# current_monitor_1_0_0.net
KiCad netlist of a schematic drawn in EAGLE
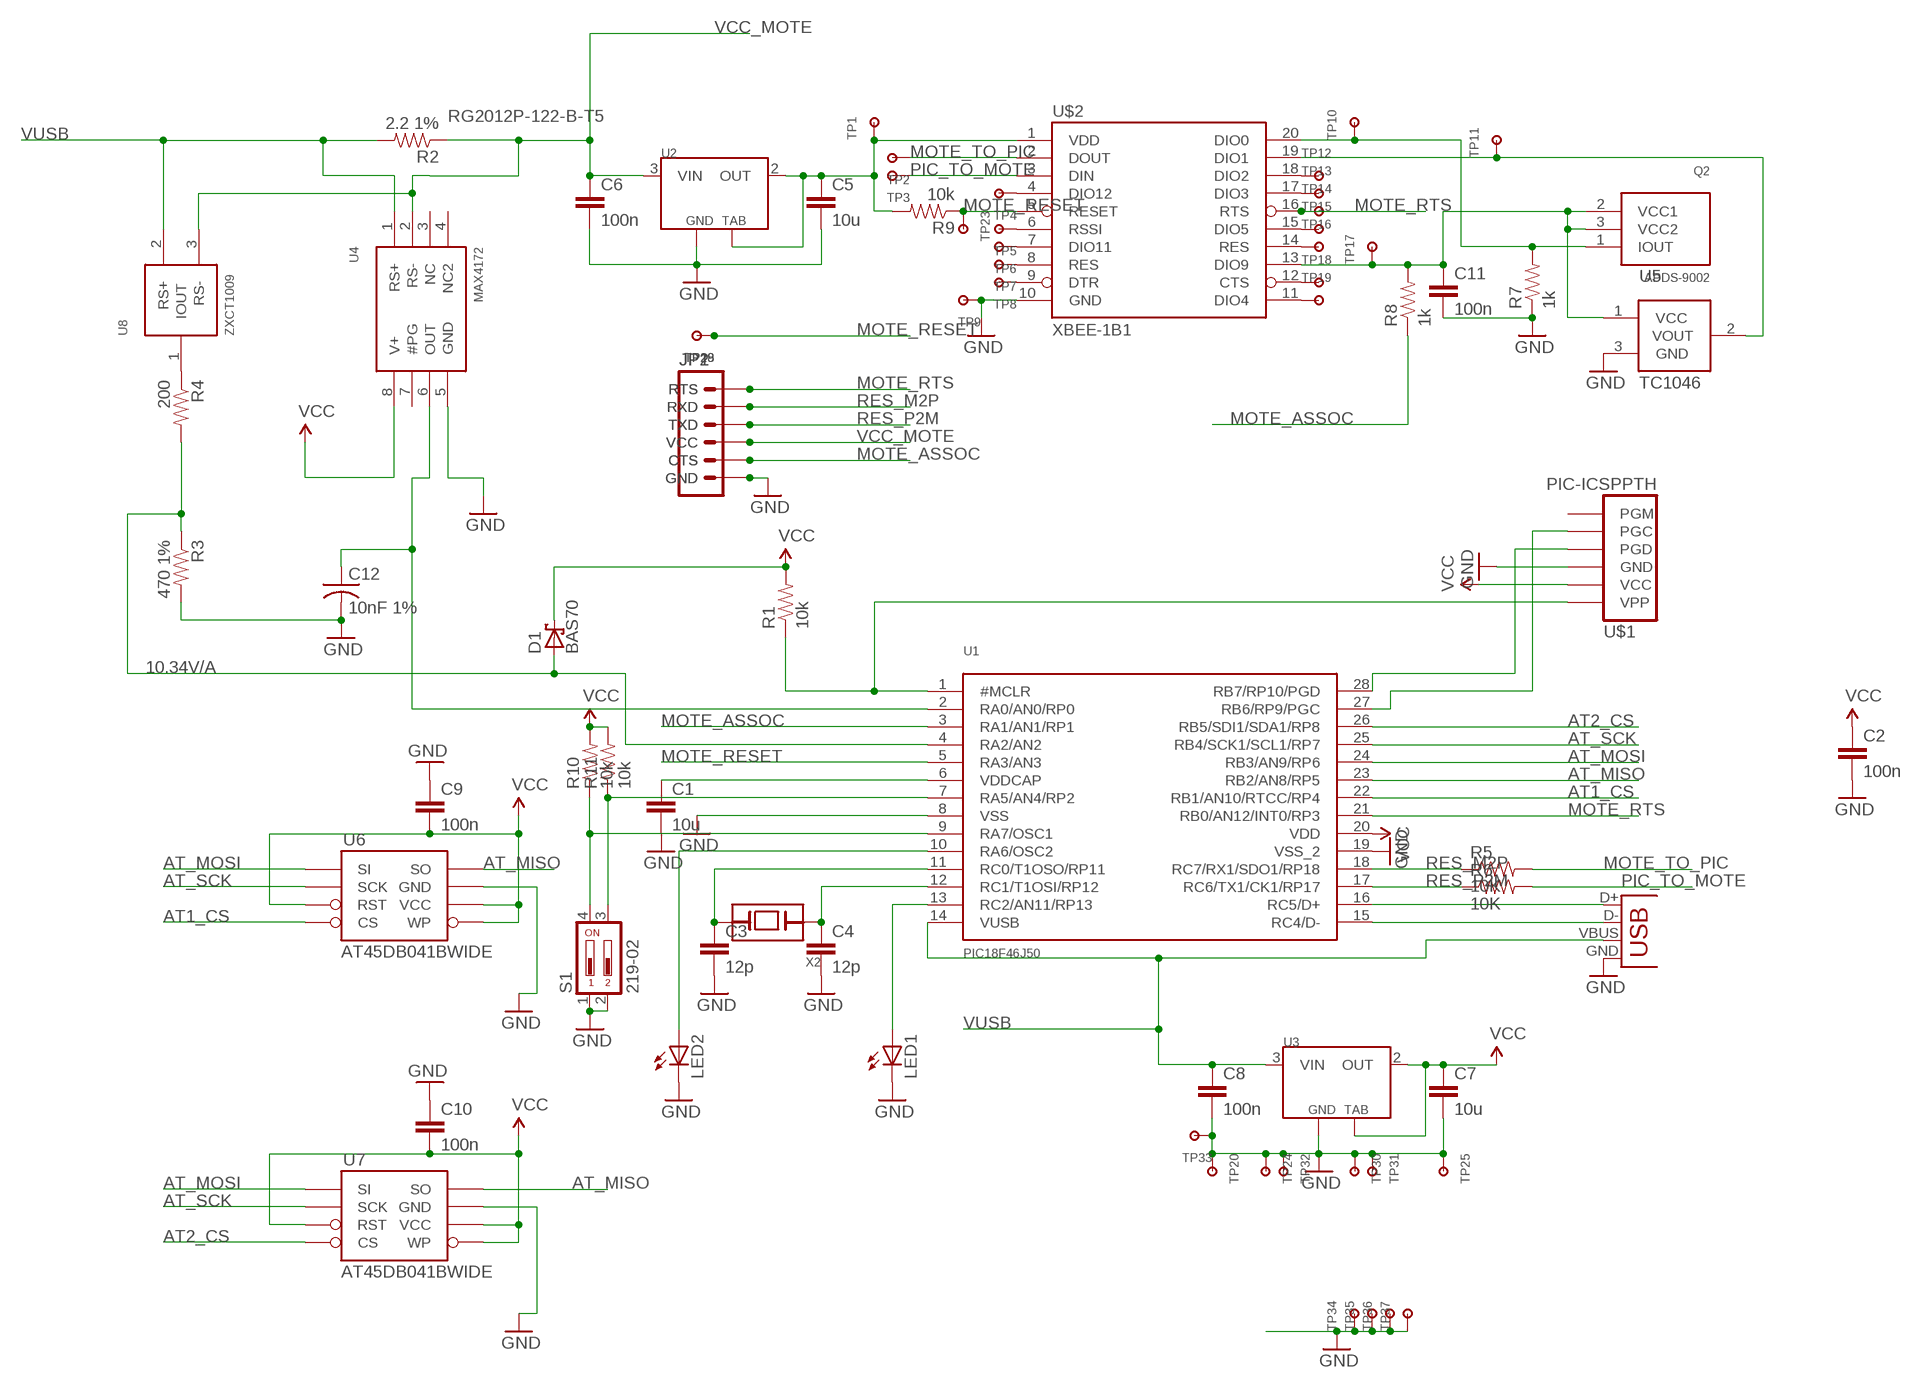
[diagram p0: schematic, sheet 1]

(export (version "E")
  (design (tool "Eeschema 10.0.6"))
  (components
    (comp (ref "C1")
      (value "10u")
      (footprint "eagle-import:0805")
      (libsource (lib "eagle-import") (part "CAP0805"))
    )
    (comp (ref "C2")
      (value "100n")
      (footprint "eagle-import:0805")
      (libsource (lib "eagle-import") (part "CAP0805"))
    )
    (comp (ref "C3")
      (value "12p")
      (footprint "eagle-import:0805")
      (libsource (lib "eagle-import") (part "CAP0805"))
    )
    (comp (ref "C4")
      (value "12p")
      (footprint "eagle-import:0805")
      (libsource (lib "eagle-import") (part "CAP0805"))
    )
    (comp (ref "C5")
      (value "10u")
      (footprint "eagle-import:0805")
      (libsource (lib "eagle-import") (part "CAP0805"))
    )
    (comp (ref "C6")
      (value "100n")
      (footprint "eagle-import:0805")
      (libsource (lib "eagle-import") (part "CAP0805"))
    )
    (comp (ref "C7")
      (value "10u")
      (footprint "eagle-import:0805")
      (libsource (lib "eagle-import") (part "CAP0805"))
    )
    (comp (ref "C8")
      (value "100n")
      (footprint "eagle-import:0805")
      (libsource (lib "eagle-import") (part "CAP0805"))
    )
    (comp (ref "C9")
      (value "100n")
      (footprint "eagle-import:0805")
      (libsource (lib "eagle-import") (part "CAP0805"))
    )
    (comp (ref "C10")
      (value "100n")
      (footprint "eagle-import:0805")
      (libsource (lib "eagle-import") (part "CAP0805"))
    )
    (comp (ref "C11")
      (value "100n")
      (footprint "eagle-import:0805")
      (libsource (lib "eagle-import") (part "CAP0805"))
    )
    (comp (ref "C12")
      (value "10nF 1%")
      (footprint "eagle-import:C1812")
      (libsource (lib "eagle-import") (part "C-USC1812"))
    )
    (comp (ref "D1")
      (value "BAS70")
      (footprint "eagle-import:SOT23")
      (libsource (lib "eagle-import") (part "BAS70"))
    )
    (comp (ref "JP1")
      (value "FTDI_CABLESIP")
      (footprint "eagle-import:1X06")
      (libsource (lib "eagle-import") (part "FTDI_CABLESIP"))
    )
    (comp (ref "JP2")
      (value "FTDI_CABLESIP")
      (footprint "eagle-import:1X06")
      (libsource (lib "eagle-import") (part "FTDI_CABLESIP"))
    )
    (comp (ref "LED1")
      (value "LEDCHIP-LED0805")
      (footprint "eagle-import:CHIP-LED0805")
      (libsource (lib "eagle-import") (part "LEDCHIP-LED0805"))
    )
    (comp (ref "LED2")
      (value "LEDCHIP-LED0805")
      (footprint "eagle-import:CHIP-LED0805")
      (libsource (lib "eagle-import") (part "LEDCHIP-LED0805"))
    )
    (comp (ref "Q2")
      (value "APDS-9002")
      (footprint "eagle-import:APDS-9002")
      (libsource (lib "eagle-import") (part "APDS-9002"))
    )
    (comp (ref "R1")
      (value "10k")
      (footprint "eagle-import:0805")
      (libsource (lib "eagle-import") (part "RESISTOR"))
    )
    (comp (ref "R2")
      (value "2.2 1%")
      (footprint "eagle-import:0805")
      (libsource (lib "eagle-import") (part "RESISTOR"))
    )
    (comp (ref "R3")
      (value "470 1%")
      (footprint "eagle-import:0805")
      (libsource (lib "eagle-import") (part "RESISTOR"))
    )
    (comp (ref "R4")
      (value "200")
      (footprint "eagle-import:0805")
      (libsource (lib "eagle-import") (part "RESISTOR"))
    )
    (comp (ref "R5")
      (value "10K")
      (footprint "eagle-import:0805")
      (libsource (lib "eagle-import") (part "RESISTOR"))
    )
    (comp (ref "R6")
      (value "10K")
      (footprint "eagle-import:0805")
      (libsource (lib "eagle-import") (part "RESISTOR"))
    )
    (comp (ref "R7")
      (value "1k")
      (footprint "eagle-import:0805")
      (libsource (lib "eagle-import") (part "RESISTOR"))
    )
    (comp (ref "R8")
      (value "1k")
      (footprint "eagle-import:0805")
      (libsource (lib "eagle-import") (part "RESISTOR"))
    )
    (comp (ref "R9")
      (value "10k")
      (footprint "eagle-import:0805")
      (libsource (lib "eagle-import") (part "RESISTOR"))
    )
    (comp (ref "R10")
      (value "10k")
      (footprint "eagle-import:0805")
      (libsource (lib "eagle-import") (part "RESISTOR"))
    )
    (comp (ref "R11")
      (value "10k")
      (footprint "eagle-import:0805")
      (libsource (lib "eagle-import") (part "RESISTOR"))
    )
    (comp (ref "S1")
      (value "219-02")
      (footprint "eagle-import:CTS-219-02")
      (libsource (lib "eagle-import") (part "219-02"))
    )
    (comp (ref "TP1")
      (value "TESTPOINT100MIL")
      (footprint "eagle-import:TESTPOINT-100MIL")
      (libsource (lib "eagle-import") (part "TESTPOINT100MIL"))
    )
    (comp (ref "TP2")
      (value "TESTPOINT100MIL")
      (footprint "eagle-import:TESTPOINT-100MIL")
      (libsource (lib "eagle-import") (part "TESTPOINT100MIL"))
    )
    (comp (ref "TP3")
      (value "TESTPOINT100MIL")
      (footprint "eagle-import:TESTPOINT-100MIL")
      (libsource (lib "eagle-import") (part "TESTPOINT100MIL"))
    )
    (comp (ref "TP4")
      (value "TESTPOINT100MIL")
      (footprint "eagle-import:TESTPOINT-100MIL")
      (libsource (lib "eagle-import") (part "TESTPOINT100MIL"))
    )
    (comp (ref "TP5")
      (value "TESTPOINT100MIL")
      (footprint "eagle-import:TESTPOINT-100MIL")
      (libsource (lib "eagle-import") (part "TESTPOINT100MIL"))
    )
    (comp (ref "TP6")
      (value "TESTPOINT100MIL")
      (footprint "eagle-import:TESTPOINT-100MIL")
      (libsource (lib "eagle-import") (part "TESTPOINT100MIL"))
    )
    (comp (ref "TP7")
      (value "TESTPOINT100MIL")
      (footprint "eagle-import:TESTPOINT-100MIL")
      (libsource (lib "eagle-import") (part "TESTPOINT100MIL"))
    )
    (comp (ref "TP8")
      (value "TESTPOINT100MIL")
      (footprint "eagle-import:TESTPOINT-100MIL")
      (libsource (lib "eagle-import") (part "TESTPOINT100MIL"))
    )
    (comp (ref "TP9")
      (value "TESTPOINT100MIL")
      (footprint "eagle-import:TESTPOINT-100MIL")
      (libsource (lib "eagle-import") (part "TESTPOINT100MIL"))
    )
    (comp (ref "TP10")
      (value "TESTPOINT100MIL")
      (footprint "eagle-import:TESTPOINT-100MIL")
      (libsource (lib "eagle-import") (part "TESTPOINT100MIL"))
    )
    (comp (ref "TP11")
      (value "TESTPOINT100MIL")
      (footprint "eagle-import:TESTPOINT-100MIL")
      (libsource (lib "eagle-import") (part "TESTPOINT100MIL"))
    )
    (comp (ref "TP12")
      (value "TESTPOINT100MIL")
      (footprint "eagle-import:TESTPOINT-100MIL")
      (libsource (lib "eagle-import") (part "TESTPOINT100MIL"))
    )
    (comp (ref "TP13")
      (value "TESTPOINT100MIL")
      (footprint "eagle-import:TESTPOINT-100MIL")
      (libsource (lib "eagle-import") (part "TESTPOINT100MIL"))
    )
    (comp (ref "TP14")
      (value "TESTPOINT100MIL")
      (footprint "eagle-import:TESTPOINT-100MIL")
      (libsource (lib "eagle-import") (part "TESTPOINT100MIL"))
    )
    (comp (ref "TP15")
      (value "TESTPOINT100MIL")
      (footprint "eagle-import:TESTPOINT-100MIL")
      (libsource (lib "eagle-import") (part "TESTPOINT100MIL"))
    )
    (comp (ref "TP16")
      (value "TESTPOINT100MIL")
      (footprint "eagle-import:TESTPOINT-100MIL")
      (libsource (lib "eagle-import") (part "TESTPOINT100MIL"))
    )
    (comp (ref "TP17")
      (value "TESTPOINT100MIL")
      (footprint "eagle-import:TESTPOINT-100MIL")
      (libsource (lib "eagle-import") (part "TESTPOINT100MIL"))
    )
    (comp (ref "TP18")
      (value "TESTPOINT100MIL")
      (footprint "eagle-import:TESTPOINT-100MIL")
      (libsource (lib "eagle-import") (part "TESTPOINT100MIL"))
    )
    (comp (ref "TP19")
      (value "TESTPOINT100MIL")
      (footprint "eagle-import:TESTPOINT-100MIL")
      (libsource (lib "eagle-import") (part "TESTPOINT100MIL"))
    )
    (comp (ref "TP20")
      (value "TESTPOINTSMALLEST")
      (footprint "eagle-import:TESTPOINT")
      (libsource (lib "eagle-import") (part "TESTPOINTSMALLEST"))
    )
    (comp (ref "TP23")
      (value "TESTPOINT100MIL")
      (footprint "eagle-import:TESTPOINT-100MIL")
      (libsource (lib "eagle-import") (part "TESTPOINT100MIL"))
    )
    (comp (ref "TP24")
      (value "TESTPOINTSMALLEST")
      (footprint "eagle-import:TESTPOINT")
      (libsource (lib "eagle-import") (part "TESTPOINTSMALLEST"))
    )
    (comp (ref "TP25")
      (value "TESTPOINTSMALLEST")
      (footprint "eagle-import:TESTPOINT")
      (libsource (lib "eagle-import") (part "TESTPOINTSMALLEST"))
    )
    (comp (ref "TP28")
      (value "TESTPOINT100MIL")
      (footprint "eagle-import:TESTPOINT-100MIL")
      (libsource (lib "eagle-import") (part "TESTPOINT100MIL"))
    )
    (comp (ref "TP29")
      (value "TESTPOINT100MIL")
      (footprint "eagle-import:TESTPOINT-100MIL")
      (libsource (lib "eagle-import") (part "TESTPOINT100MIL"))
    )
    (comp (ref "TP30")
      (value "TESTPOINTSMALLEST")
      (footprint "eagle-import:TESTPOINT")
      (libsource (lib "eagle-import") (part "TESTPOINTSMALLEST"))
    )
    (comp (ref "TP31")
      (value "TESTPOINTSMALLEST")
      (footprint "eagle-import:TESTPOINT")
      (libsource (lib "eagle-import") (part "TESTPOINTSMALLEST"))
    )
    (comp (ref "TP32")
      (value "TESTPOINTSMALLEST")
      (footprint "eagle-import:TESTPOINT")
      (libsource (lib "eagle-import") (part "TESTPOINTSMALLEST"))
    )
    (comp (ref "TP33")
      (value "TESTPOINTSMALLEST")
      (footprint "eagle-import:TESTPOINT")
      (libsource (lib "eagle-import") (part "TESTPOINTSMALLEST"))
    )
    (comp (ref "TP34")
      (value "TESTPOINTM3")
      (footprint "eagle-import:M3_HOLE")
      (libsource (lib "eagle-import") (part "TESTPOINTM3"))
    )
    (comp (ref "TP35")
      (value "TESTPOINTM3")
      (footprint "eagle-import:M3_HOLE")
      (libsource (lib "eagle-import") (part "TESTPOINTM3"))
    )
    (comp (ref "TP36")
      (value "TESTPOINTM3")
      (footprint "eagle-import:M3_HOLE")
      (libsource (lib "eagle-import") (part "TESTPOINTM3"))
    )
    (comp (ref "TP37")
      (value "TESTPOINTM3")
      (footprint "eagle-import:M3_HOLE")
      (libsource (lib "eagle-import") (part "TESTPOINTM3"))
    )
    (comp (ref "U$1")
      (value "PIC-ICSPPTH")
      (footprint "eagle-import:MOLEX-1X6")
      (libsource (lib "eagle-import") (part "PIC-ICSPPTH"))
    )
    (comp (ref "U$2")
      (value "XBEE-1B1")
      (footprint "eagle-import:XBEE-1")
      (libsource (lib "eagle-import") (part "XBEE-1B1"))
    )
    (comp (ref "U1")
      (value "PIC18F46J50")
      (footprint "eagle-import:SO28W")
      (libsource (lib "eagle-import") (part "PIC18F46J50"))
    )
    (comp (ref "U2")
      (value "NX1117C")
      (footprint "eagle-import:SOT223")
      (libsource (lib "eagle-import") (part "NX1117C"))
    )
    (comp (ref "U3")
      (value "NX1117C")
      (footprint "eagle-import:SOT223")
      (libsource (lib "eagle-import") (part "NX1117C"))
    )
    (comp (ref "U4")
      (value "MAX4172")
      (footprint "eagle-import:SO08")
      (libsource (lib "eagle-import") (part "MAX4172"))
    )
    (comp (ref "U5")
      (value "TC1046")
      (footprint "eagle-import:SOT23")
      (libsource (lib "eagle-import") (part "TC1046"))
    )
    (comp (ref "U6")
      (value "AT45DB041BWIDE")
      (footprint "eagle-import:SO08WIDE")
      (libsource (lib "eagle-import") (part "AT45DB041BWIDE"))
    )
    (comp (ref "U7")
      (value "AT45DB041BWIDE")
      (footprint "eagle-import:SO08WIDE")
      (libsource (lib "eagle-import") (part "AT45DB041BWIDE"))
    )
    (comp (ref "U8")
      (value "ZXCT1009")
      (footprint "eagle-import:SOT23")
      (libsource (lib "eagle-import") (part "ZXCT1009"))
    )
    (comp (ref "X1")
      (value "USBSMD")
      (footprint "eagle-import:USB-MINIB")
      (libsource (lib "eagle-import") (part "USBSMD"))
    )
    (comp (ref "X2")
      (value "XTALABS07")
      (footprint "eagle-import:ABS07")
      (libsource (lib "eagle-import") (part "XTALABS07"))
    )
  )
  (nets
    (net (code "1") (name "/AT1_CS") (class "Default")
      (node (ref "U1") (pin "22") (pinfunction "RB1/AN10/RTCC/RP4_22") (pintype "bidirectional"))
      (node (ref "U6") (pin "4") (pinfunction "CS_4") (pintype "bidirectional"))
    )
    (net (code "2") (name "/AT2_CS") (class "Default")
      (node (ref "U1") (pin "26") (pinfunction "RB5/SDI1/SDA1/RP8_26") (pintype "bidirectional"))
      (node (ref "U7") (pin "4") (pinfunction "CS_4") (pintype "bidirectional"))
    )
    (net (code "3") (name "/AT_MISO") (class "Default")
      (node (ref "U1") (pin "23") (pinfunction "RB2/AN8/RP5_23") (pintype "bidirectional"))
      (node (ref "U6") (pin "8") (pinfunction "SO_8") (pintype "bidirectional"))
      (node (ref "U7") (pin "8") (pinfunction "SO_8") (pintype "bidirectional"))
    )
    (net (code "4") (name "/AT_MOSI") (class "Default")
      (node (ref "U1") (pin "24") (pinfunction "RB3/AN9/RP6_24") (pintype "bidirectional"))
      (node (ref "U6") (pin "1") (pinfunction "SI_1") (pintype "bidirectional"))
      (node (ref "U7") (pin "1") (pinfunction "SI_1") (pintype "bidirectional"))
    )
    (net (code "5") (name "/AT_SCK") (class "Default")
      (node (ref "U1") (pin "25") (pinfunction "RB4/SCK1/SCL1/RP7_25") (pintype "bidirectional"))
      (node (ref "U6") (pin "2") (pinfunction "SCK_2") (pintype "bidirectional"))
      (node (ref "U7") (pin "2") (pinfunction "SCK_2") (pintype "bidirectional"))
    )
    (net (code "6") (name "/MOTE_ASSOC") (class "Default")
      (node (ref "JP1") (pin "2") (pinfunction "CTS_2") (pintype "passive"))
      (node (ref "JP2") (pin "2") (pinfunction "CTS_2") (pintype "passive"))
      (node (ref "R8") (pin "1") (pinfunction "1_1") (pintype "passive"))
      (node (ref "U1") (pin "3") (pinfunction "RA1/AN1/RP1_3") (pintype "bidirectional"))
    )
    (net (code "7") (name "/MOTE_RESET") (class "Default")
      (node (ref "R9") (pin "1") (pinfunction "1_1") (pintype "passive"))
      (node (ref "TP23") (pin "2") (pinfunction "P$1_2") (pintype "bidirectional"))
      (node (ref "TP28") (pin "2") (pinfunction "P$1_2") (pintype "bidirectional"))
      (node (ref "TP29") (pin "2") (pinfunction "P$1_2") (pintype "bidirectional"))
      (node (ref "U$2") (pin "5") (pinfunction "RESET_5") (pintype "input"))
      (node (ref "U1") (pin "5") (pinfunction "RA3/AN3_5") (pintype "bidirectional"))
    )
    (net (code "8") (name "/MOTE_RTS") (class "Default")
      (node (ref "JP1") (pin "6") (pinfunction "RTS_6") (pintype "passive"))
      (node (ref "JP2") (pin "6") (pinfunction "RTS_6") (pintype "passive"))
      (node (ref "TP14") (pin "2") (pinfunction "P$1_2") (pintype "bidirectional"))
      (node (ref "U$2") (pin "16") (pinfunction "RTS_16") (pintype "input"))
      (node (ref "U1") (pin "21") (pinfunction "RB0/AN12/INT0/RP3_21") (pintype "bidirectional"))
    )
    (net (code "9") (name "/MOTE_TO_PIC") (class "Default")
      (node (ref "R5") (pin "2") (pinfunction "2_2") (pintype "passive"))
      (node (ref "TP2") (pin "2") (pinfunction "P$1_2") (pintype "bidirectional"))
      (node (ref "U$2") (pin "2") (pinfunction "DOUT_2") (pintype "output"))
    )
    (net (code "10") (name "/PIC_TO_MOTE") (class "Default")
      (node (ref "R6") (pin "2") (pinfunction "2_2") (pintype "passive"))
      (node (ref "TP3") (pin "2") (pinfunction "P$1_2") (pintype "bidirectional"))
      (node (ref "U$2") (pin "3") (pinfunction "DIN_3") (pintype "input"))
    )
    (net (code "11") (name "/RES_M2P") (class "Default")
      (node (ref "JP1") (pin "5") (pinfunction "RXD_5") (pintype "passive"))
      (node (ref "JP2") (pin "5") (pinfunction "RXD_5") (pintype "passive"))
      (node (ref "R5") (pin "1") (pinfunction "1_1") (pintype "passive"))
      (node (ref "U1") (pin "18") (pinfunction "RC7/RX1/SDO1/RP18_18") (pintype "bidirectional"))
    )
    (net (code "12") (name "/RES_P2M") (class "Default")
      (node (ref "JP1") (pin "4") (pinfunction "TXD_4") (pintype "passive"))
      (node (ref "JP2") (pin "4") (pinfunction "TXD_4") (pintype "passive"))
      (node (ref "R6") (pin "1") (pinfunction "1_1") (pintype "passive"))
      (node (ref "U1") (pin "17") (pinfunction "RC6/TX1/CK1/RP17_17") (pintype "bidirectional"))
    )
    (net (code "13") (name "/VCC_MOTE") (class "Default")
      (node (ref "C6") (pin "1") (pinfunction "1_1") (pintype "passive"))
      (node (ref "JP1") (pin "3") (pinfunction "VCC_3") (pintype "passive"))
      (node (ref "JP2") (pin "3") (pinfunction "VCC_3") (pintype "passive"))
      (node (ref "R2") (pin "1") (pinfunction "1_1") (pintype "passive"))
      (node (ref "U2") (pin "3") (pinfunction "VIN_3") (pintype "bidirectional"))
      (node (ref "U4") (pin "2") (pinfunction "RS-_2") (pintype "bidirectional"))
      (node (ref "U8") (pin "3") (pinfunction "RS-_3") (pintype "bidirectional"))
    )
    (net (code "14") (name "/VUSB") (class "Default")
      (node (ref "C8") (pin "1") (pinfunction "1_1") (pintype "passive"))
      (node (ref "R2") (pin "2") (pinfunction "2_2") (pintype "passive"))
      (node (ref "U1") (pin "14") (pinfunction "VUSB_14") (pintype "bidirectional"))
      (node (ref "U3") (pin "3") (pinfunction "VIN_3") (pintype "bidirectional"))
      (node (ref "U4") (pin "1") (pinfunction "RS+_1") (pintype "bidirectional"))
      (node (ref "U8") (pin "2") (pinfunction "RS+_2") (pintype "bidirectional"))
      (node (ref "X1") (pin "VBUS") (pinfunction "VBUS_VBUS") (pintype "bidirectional"))
    )
    (net (code "15") (name "GND") (class "Default")
      (node (ref "C1") (pin "2") (pinfunction "2_2") (pintype "passive"))
      (node (ref "C10") (pin "1") (pinfunction "1_1") (pintype "passive"))
      (node (ref "C11") (pin "2") (pinfunction "2_2") (pintype "passive"))
      (node (ref "C12") (pin "2") (pinfunction "2_2") (pintype "passive"))
      (node (ref "C2") (pin "2") (pinfunction "2_2") (pintype "passive"))
      (node (ref "C3") (pin "2") (pinfunction "2_2") (pintype "passive"))
      (node (ref "C4") (pin "2") (pinfunction "2_2") (pintype "passive"))
      (node (ref "C5") (pin "2") (pinfunction "2_2") (pintype "passive"))
      (node (ref "C6") (pin "2") (pinfunction "2_2") (pintype "passive"))
      (node (ref "C7") (pin "2") (pinfunction "2_2") (pintype "passive"))
      (node (ref "C8") (pin "2") (pinfunction "2_2") (pintype "passive"))
      (node (ref "C9") (pin "1") (pinfunction "1_1") (pintype "passive"))
      (node (ref "JP1") (pin "1") (pinfunction "GND_1") (pintype "passive"))
      (node (ref "JP2") (pin "1") (pinfunction "GND_1") (pintype "passive"))
      (node (ref "LED1") (pin "C") (pinfunction "C_C") (pintype "passive"))
      (node (ref "LED2") (pin "C") (pinfunction "C_C") (pintype "passive"))
      (node (ref "R3") (pin "2") (pinfunction "2_2") (pintype "passive"))
      (node (ref "R7") (pin "1") (pinfunction "1_1") (pintype "passive"))
      (node (ref "S1") (pin "1") (pinfunction "1_1") (pintype "passive"))
      (node (ref "S1") (pin "2") (pinfunction "2_2") (pintype "passive"))
      (node (ref "TP20") (pin "P$1") (pinfunction "P$1_P$1") (pintype "bidirectional"))
      (node (ref "TP24") (pin "P$1") (pinfunction "P$1_P$1") (pintype "bidirectional"))
      (node (ref "TP25") (pin "P$1") (pinfunction "P$1_P$1") (pintype "bidirectional"))
      (node (ref "TP30") (pin "P$1") (pinfunction "P$1_P$1") (pintype "bidirectional"))
      (node (ref "TP31") (pin "P$1") (pinfunction "P$1_P$1") (pintype "bidirectional"))
      (node (ref "TP32") (pin "P$1") (pinfunction "P$1_P$1") (pintype "bidirectional"))
      (node (ref "TP33") (pin "P$1") (pinfunction "P$1_P$1") (pintype "bidirectional"))
      (node (ref "TP34") (pin "P$1") (pinfunction "P$1_P$1") (pintype "bidirectional"))
      (node (ref "TP35") (pin "P$1") (pinfunction "P$1_P$1") (pintype "bidirectional"))
      (node (ref "TP36") (pin "P$1") (pinfunction "P$1_P$1") (pintype "bidirectional"))
      (node (ref "TP37") (pin "P$1") (pinfunction "P$1_P$1") (pintype "bidirectional"))
      (node (ref "TP9") (pin "2") (pinfunction "P$1_2") (pintype "bidirectional"))
      (node (ref "U$1") (pin "4") (pinfunction "GND_4") (pintype "bidirectional"))
      (node (ref "U$2") (pin "10") (pinfunction "GND_10") (pintype "power_in"))
      (node (ref "U1") (pin "19") (pinfunction "VSS_2_19") (pintype "bidirectional"))
      (node (ref "U1") (pin "8") (pinfunction "VSS_8") (pintype "bidirectional"))
      (node (ref "U2") (pin "1") (pinfunction "GND_1") (pintype "bidirectional"))
      (node (ref "U3") (pin "1") (pinfunction "GND_1") (pintype "bidirectional"))
      (node (ref "U4") (pin "5") (pinfunction "GND_5") (pintype "bidirectional"))
      (node (ref "U5") (pin "3") (pinfunction "GND_3") (pintype "bidirectional"))
      (node (ref "U6") (pin "7") (pinfunction "GND_7") (pintype "bidirectional"))
      (node (ref "U7") (pin "7") (pinfunction "GND_7") (pintype "bidirectional"))
      (node (ref "X1") (pin "GND") (pinfunction "GND_GND") (pintype "bidirectional"))
    )
    (net (code "16") (name "Net-(D1-A)") (class "Default")
      (node (ref "D1") (pin "1") (pinfunction "A_1") (pintype "passive"))
      (node (ref "R3") (pin "1") (pinfunction "1_1") (pintype "passive"))
      (node (ref "R4") (pin "2") (pinfunction "2_2") (pintype "passive"))
      (node (ref "U1") (pin "4") (pinfunction "RA2/AN2_4") (pintype "bidirectional"))
    )
    (net (code "17") (name "Net-(Q2-IOUT)") (class "Default")
      (node (ref "Q2") (pin "1") (pinfunction "IOUT_1") (pintype "bidirectional"))
      (node (ref "R7") (pin "2") (pinfunction "2_2") (pintype "passive"))
      (node (ref "TP10") (pin "2") (pinfunction "P$1_2") (pintype "bidirectional"))
      (node (ref "U$2") (pin "20") (pinfunction "DIO0_20") (pintype "bidirectional"))
    )
    (net (code "18") (name "Net-(Q2-VCC1)") (class "Default")
      (node (ref "C11") (pin "1") (pinfunction "1_1") (pintype "passive"))
      (node (ref "Q2") (pin "2") (pinfunction "VCC1_2") (pintype "bidirectional"))
      (node (ref "Q2") (pin "3") (pinfunction "VCC2_3") (pintype "bidirectional"))
      (node (ref "R8") (pin "2") (pinfunction "2_2") (pintype "passive"))
      (node (ref "TP17") (pin "2") (pinfunction "P$1_2") (pintype "bidirectional"))
      (node (ref "U$2") (pin "13") (pinfunction "DIO9_13") (pintype "bidirectional"))
      (node (ref "U5") (pin "1") (pinfunction "VCC_1") (pintype "bidirectional"))
    )
    (net (code "19") (name "Net-(TP1-P$1)") (class "Default")
      (node (ref "C5") (pin "1") (pinfunction "1_1") (pintype "passive"))
      (node (ref "R9") (pin "2") (pinfunction "2_2") (pintype "passive"))
      (node (ref "TP1") (pin "2") (pinfunction "P$1_2") (pintype "bidirectional"))
      (node (ref "U$2") (pin "1") (pinfunction "VDD_1") (pintype "power_in"))
      (node (ref "U2") (pin "2") (pinfunction "OUT_2") (pintype "bidirectional"))
      (node (ref "U2") (pin "4") (pinfunction "TAB_4") (pintype "bidirectional"))
    )
    (net (code "20") (name "Net-(TP4-P$1)") (class "Default")
      (node (ref "TP4") (pin "2") (pinfunction "P$1_2") (pintype "bidirectional"))
      (node (ref "U$2") (pin "4") (pinfunction "DIO12_4") (pintype "bidirectional"))
    )
    (net (code "21") (name "Net-(TP5-P$1)") (class "Default")
      (node (ref "TP5") (pin "2") (pinfunction "P$1_2") (pintype "bidirectional"))
      (node (ref "U$2") (pin "6") (pinfunction "RSSI_6") (pintype "bidirectional"))
    )
    (net (code "22") (name "Net-(TP6-P$1)") (class "Default")
      (node (ref "TP6") (pin "2") (pinfunction "P$1_2") (pintype "bidirectional"))
      (node (ref "U$2") (pin "7") (pinfunction "DIO11_7") (pintype "bidirectional"))
    )
    (net (code "23") (name "Net-(TP7-P$1)") (class "Default")
      (node (ref "TP7") (pin "2") (pinfunction "P$1_2") (pintype "bidirectional"))
      (node (ref "U$2") (pin "8") (pinfunction "RES_8") (pintype "bidirectional"))
    )
    (net (code "24") (name "Net-(TP8-P$1)") (class "Default")
      (node (ref "TP8") (pin "2") (pinfunction "P$1_2") (pintype "bidirectional"))
      (node (ref "U$2") (pin "9") (pinfunction "DTR_9") (pintype "bidirectional"))
    )
    (net (code "25") (name "Net-(TP11-P$1)") (class "Default")
      (node (ref "TP11") (pin "2") (pinfunction "P$1_2") (pintype "bidirectional"))
      (node (ref "U$2") (pin "19") (pinfunction "DIO1_19") (pintype "bidirectional"))
      (node (ref "U5") (pin "2") (pinfunction "VOUT_2") (pintype "bidirectional"))
    )
    (net (code "26") (name "Net-(TP12-P$1)") (class "Default")
      (node (ref "TP12") (pin "2") (pinfunction "P$1_2") (pintype "bidirectional"))
      (node (ref "U$2") (pin "18") (pinfunction "DIO2_18") (pintype "bidirectional"))
    )
    (net (code "27") (name "Net-(TP13-P$1)") (class "Default")
      (node (ref "TP13") (pin "2") (pinfunction "P$1_2") (pintype "bidirectional"))
      (node (ref "U$2") (pin "17") (pinfunction "DIO3_17") (pintype "bidirectional"))
    )
    (net (code "28") (name "Net-(TP15-P$1)") (class "Default")
      (node (ref "TP15") (pin "2") (pinfunction "P$1_2") (pintype "bidirectional"))
      (node (ref "U$2") (pin "15") (pinfunction "DIO5_15") (pintype "bidirectional"))
    )
    (net (code "29") (name "Net-(TP16-P$1)") (class "Default")
      (node (ref "TP16") (pin "2") (pinfunction "P$1_2") (pintype "bidirectional"))
      (node (ref "U$2") (pin "14") (pinfunction "RES_14") (pintype "bidirectional"))
    )
    (net (code "30") (name "Net-(TP18-P$1)") (class "Default")
      (node (ref "TP18") (pin "2") (pinfunction "P$1_2") (pintype "bidirectional"))
      (node (ref "U$2") (pin "12") (pinfunction "CTS_12") (pintype "output"))
    )
    (net (code "31") (name "Net-(TP19-P$1)") (class "Default")
      (node (ref "TP19") (pin "2") (pinfunction "P$1_2") (pintype "bidirectional"))
      (node (ref "U$2") (pin "11") (pinfunction "DIO4_11") (pintype "bidirectional"))
    )
    (net (code "32") (name "Net-(U$1-PGC)") (class "Default")
      (node (ref "U$1") (pin "2") (pinfunction "PGC_2") (pintype "bidirectional"))
      (node (ref "U1") (pin "27") (pinfunction "RB6/RP9/PGC_27") (pintype "bidirectional"))
    )
    (net (code "33") (name "Net-(U$1-PGD)") (class "Default")
      (node (ref "U$1") (pin "3") (pinfunction "PGD_3") (pintype "bidirectional"))
      (node (ref "U1") (pin "28") (pinfunction "RB7/RP10/PGD_28") (pintype "bidirectional"))
    )
    (net (code "34") (name "Net-(U$1-VPP)") (class "Default")
      (node (ref "R1") (pin "1") (pinfunction "1_1") (pintype "passive"))
      (node (ref "U$1") (pin "6") (pinfunction "VPP_6") (pintype "bidirectional"))
      (node (ref "U1") (pin "1") (pinfunction "#MCLR_1") (pintype "bidirectional"))
    )
    (net (code "35") (name "Net-(U1-RA0{slash}AN0{slash}RP0)") (class "Default")
      (node (ref "C12") (pin "1") (pinfunction "1_1") (pintype "passive"))
      (node (ref "U1") (pin "2") (pinfunction "RA0/AN0/RP0_2") (pintype "bidirectional"))
      (node (ref "U4") (pin "6") (pinfunction "OUT_6") (pintype "bidirectional"))
    )
    (net (code "36") (name "Net-(U1-RA5{slash}AN4{slash}RP2)") (class "Default")
      (node (ref "R11") (pin "1") (pinfunction "1_1") (pintype "passive"))
      (node (ref "S1") (pin "3") (pinfunction "3_3") (pintype "passive"))
      (node (ref "U1") (pin "7") (pinfunction "RA5/AN4/RP2_7") (pintype "bidirectional"))
    )
    (net (code "37") (name "Net-(U1-RA6{slash}OSC2)") (class "Default")
      (node (ref "LED2") (pin "A") (pinfunction "A_A") (pintype "passive"))
      (node (ref "U1") (pin "10") (pinfunction "RA6/OSC2_10") (pintype "bidirectional"))
    )
    (net (code "38") (name "Net-(U1-RA7{slash}OSC1)") (class "Default")
      (node (ref "R10") (pin "1") (pinfunction "1_1") (pintype "passive"))
      (node (ref "S1") (pin "4") (pinfunction "4_4") (pintype "passive"))
      (node (ref "U1") (pin "9") (pinfunction "RA7/OSC1_9") (pintype "bidirectional"))
    )
    (net (code "39") (name "Net-(U1-RC0{slash}T1OSO{slash}RP11)") (class "Default")
      (node (ref "C3") (pin "1") (pinfunction "1_1") (pintype "passive"))
      (node (ref "U1") (pin "11") (pinfunction "RC0/T1OSO/RP11_11") (pintype "bidirectional"))
      (node (ref "X2") (pin "2") (pinfunction "B_2") (pintype "bidirectional"))
    )
    (net (code "40") (name "Net-(U1-RC1{slash}T1OSI{slash}RP12)") (class "Default")
      (node (ref "C4") (pin "1") (pinfunction "1_1") (pintype "passive"))
      (node (ref "U1") (pin "12") (pinfunction "RC1/T1OSI/RP12_12") (pintype "bidirectional"))
      (node (ref "X2") (pin "1") (pinfunction "A_1") (pintype "bidirectional"))
    )
    (net (code "41") (name "Net-(U1-RC2{slash}AN11{slash}RP13)") (class "Default")
      (node (ref "LED1") (pin "A") (pinfunction "A_A") (pintype "passive"))
      (node (ref "U1") (pin "13") (pinfunction "RC2/AN11/RP13_13") (pintype "bidirectional"))
    )
    (net (code "42") (name "Net-(U1-RC4{slash}D-)") (class "Default")
      (node (ref "U1") (pin "15") (pinfunction "RC4/D-_15") (pintype "bidirectional"))
      (node (ref "X1") (pin "D-") (pinfunction "D-_D-") (pintype "bidirectional"))
    )
    (net (code "43") (name "Net-(U1-RC5{slash}D+)") (class "Default")
      (node (ref "U1") (pin "16") (pinfunction "RC5/D+_16") (pintype "bidirectional"))
      (node (ref "X1") (pin "D+") (pinfunction "D+_D+") (pintype "bidirectional"))
    )
    (net (code "44") (name "Net-(U1-VDDCAP)") (class "Default")
      (node (ref "C1") (pin "1") (pinfunction "1_1") (pintype "passive"))
      (node (ref "U1") (pin "6") (pinfunction "VDDCAP_6") (pintype "bidirectional"))
    )
    (net (code "45") (name "Net-(U8-IOUT)") (class "Default")
      (node (ref "R4") (pin "1") (pinfunction "1_1") (pintype "passive"))
      (node (ref "U8") (pin "1") (pinfunction "IOUT_1") (pintype "bidirectional"))
    )
    (net (code "46") (name "VCC") (class "Default")
      (node (ref "C10") (pin "2") (pinfunction "2_2") (pintype "passive"))
      (node (ref "C2") (pin "1") (pinfunction "1_1") (pintype "passive"))
      (node (ref "C7") (pin "1") (pinfunction "1_1") (pintype "passive"))
      (node (ref "C9") (pin "2") (pinfunction "2_2") (pintype "passive"))
      (node (ref "D1") (pin "3") (pinfunction "C_3") (pintype "passive"))
      (node (ref "R1") (pin "2") (pinfunction "2_2") (pintype "passive"))
      (node (ref "R10") (pin "2") (pinfunction "2_2") (pintype "passive"))
      (node (ref "R11") (pin "2") (pinfunction "2_2") (pintype "passive"))
      (node (ref "U$1") (pin "5") (pinfunction "VCC_5") (pintype "bidirectional"))
      (node (ref "U1") (pin "20") (pinfunction "VDD_20") (pintype "bidirectional"))
      (node (ref "U3") (pin "2") (pinfunction "OUT_2") (pintype "bidirectional"))
      (node (ref "U3") (pin "4") (pinfunction "TAB_4") (pintype "bidirectional"))
      (node (ref "U4") (pin "8") (pinfunction "V+_8") (pintype "bidirectional"))
      (node (ref "U6") (pin "3") (pinfunction "RST_3") (pintype "bidirectional"))
      (node (ref "U6") (pin "5") (pinfunction "WP_5") (pintype "bidirectional"))
      (node (ref "U6") (pin "6") (pinfunction "VCC_6") (pintype "bidirectional"))
      (node (ref "U7") (pin "3") (pinfunction "RST_3") (pintype "bidirectional"))
      (node (ref "U7") (pin "5") (pinfunction "WP_5") (pintype "bidirectional"))
      (node (ref "U7") (pin "6") (pinfunction "VCC_6") (pintype "bidirectional"))
    )
    (net (code "47") (name "unconnected-(U$1-PGM-Pad1)") (class "Default")
      (node (ref "U$1") (pin "1") (pinfunction "PGM_1") (pintype "bidirectional"))
    )
    (net (code "48") (name "unconnected-(U4-#PG-Pad7)") (class "Default")
      (node (ref "U4") (pin "7") (pinfunction "#PG_7") (pintype "bidirectional"))
    )
    (net (code "49") (name "unconnected-(U4-NC-Pad3)") (class "Default")
      (node (ref "U4") (pin "3") (pinfunction "NC_3") (pintype "bidirectional"))
    )
    (net (code "50") (name "unconnected-(U4-NC2-Pad4)") (class "Default")
      (node (ref "U4") (pin "4") (pinfunction "NC2_4") (pintype "bidirectional"))
    )
  )
)
